# SensorStick_IMUedits.net
KiCad netlist of a schematic drawn in EAGLE
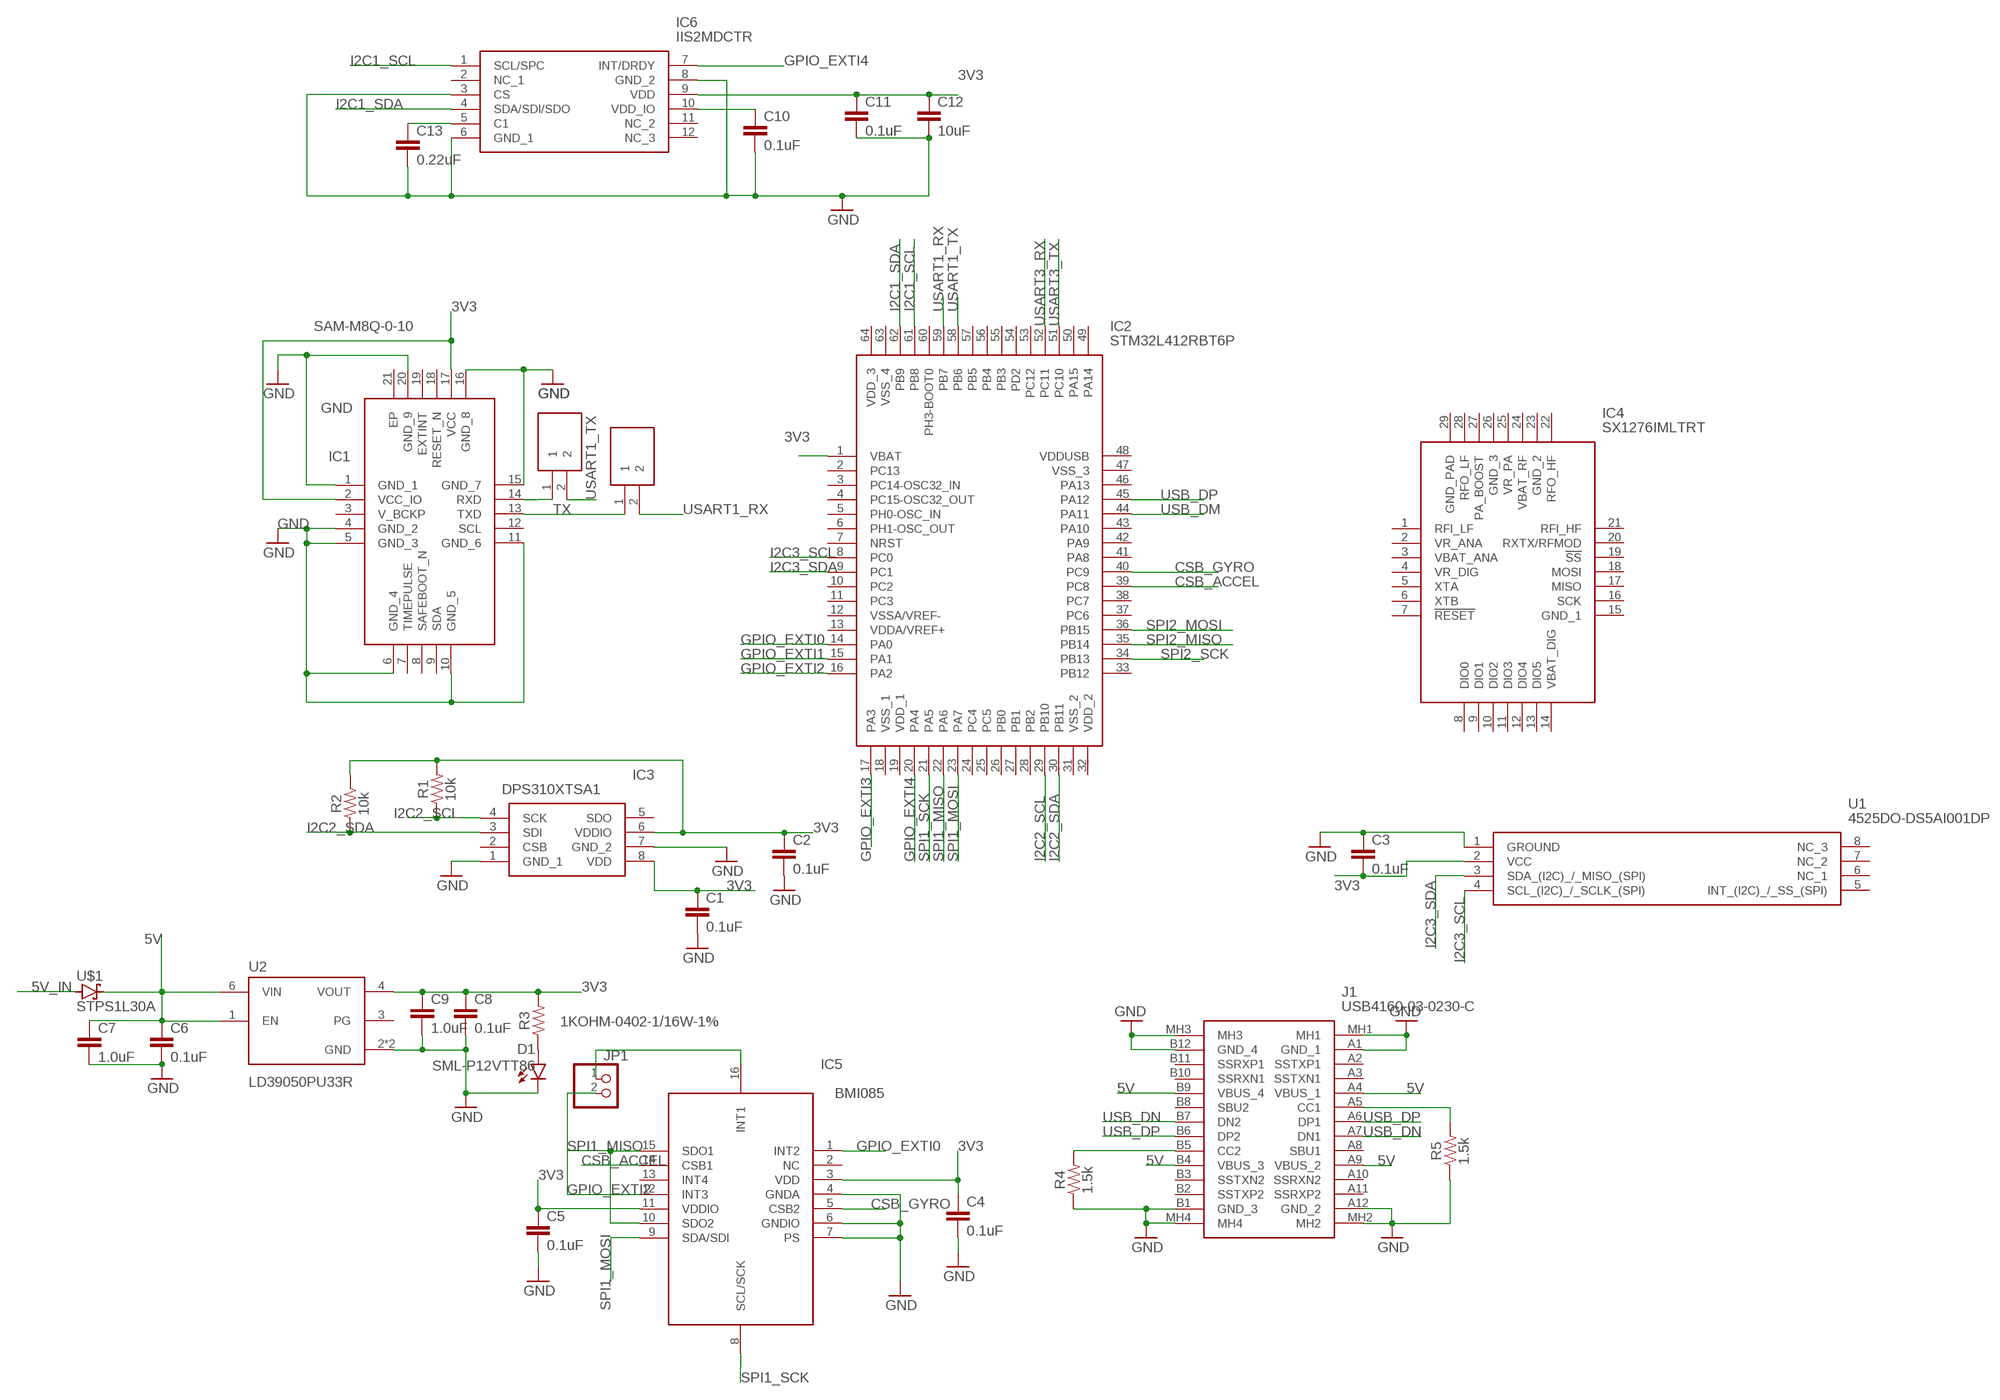
[diagram p0: schematic, sheet 1]

(export (version "E")
  (design (tool "Eeschema 10.0.6"))
  (components
    (comp (ref "C1")
      (value "0.1uF")
      (footprint "eagle-import:0402")
      (libsource (lib "eagle-import") (part "0.1UF-0402-6.3V-10%-X7R"))
    )
    (comp (ref "C2")
      (value "0.1uF")
      (footprint "eagle-import:0402")
      (libsource (lib "eagle-import") (part "0.1UF-0402-6.3V-10%-X7R"))
    )
    (comp (ref "C3")
      (value "0.1uF")
      (footprint "eagle-import:0402")
      (libsource (lib "eagle-import") (part "0.1UF-0402-6.3V-10%-X7R"))
    )
    (comp (ref "C4")
      (value "0.1uF")
      (footprint "eagle-import:0402")
      (libsource (lib "eagle-import") (part "0.1UF-0402-6.3V-10%-X7R"))
    )
    (comp (ref "C5")
      (value "0.1uF")
      (footprint "eagle-import:0402")
      (libsource (lib "eagle-import") (part "0.1UF-0402-6.3V-10%-X7R"))
    )
    (comp (ref "C6")
      (value "0.1uF")
      (footprint "eagle-import:0402")
      (libsource (lib "eagle-import") (part "0.1UF-0402-6.3V-10%-X7R"))
    )
    (comp (ref "C7")
      (value "1.0uF")
      (footprint "eagle-import:0402")
      (libsource (lib "eagle-import") (part "1.0UF-0402-16V-10%"))
    )
    (comp (ref "C8")
      (value "0.1uF")
      (footprint "eagle-import:0402")
      (libsource (lib "eagle-import") (part "0.1UF-0402-6.3V-10%-X7R"))
    )
    (comp (ref "C9")
      (value "1.0uF")
      (footprint "eagle-import:0402")
      (libsource (lib "eagle-import") (part "1.0UF-0402-16V-10%"))
    )
    (comp (ref "C10")
      (value "0.1uF")
      (footprint "eagle-import:0402")
      (libsource (lib "eagle-import") (part "0.1UF-0402-6.3V-10%-X7R"))
    )
    (comp (ref "C11")
      (value "0.1uF")
      (footprint "eagle-import:0402")
      (libsource (lib "eagle-import") (part "0.1UF-0402-6.3V-10%-X7R"))
    )
    (comp (ref "C12")
      (value "10uF")
      (footprint "eagle-import:0603")
      (libsource (lib "eagle-import") (part "10UF-0603-6.3V-20%"))
    )
    (comp (ref "C13")
      (value "0.22uF")
      (footprint "eagle-import:0603")
      (libsource (lib "eagle-import") (part "0.22UF-0603-25V-10%"))
    )
    (comp (ref "D1")
      (value "SML-P12VTT86")
      (footprint "eagle-import:LED_SML-P11UTT86R")
      (fields (field (name "MF") "Rohm"))
      (libsource (lib "eagle-import") (part "SML-P12VTT86"))
    )
    (comp (ref "FB1")
      (value "BLM15HD102SN1")
      (footprint "eagle-import:NFZ15SG152SN10B")
      (libsource (lib "eagle-import") (part "BLM15HD102SN1"))
    )
    (comp (ref "FB2")
      (value "BLM15HD102SN1")
      (footprint "eagle-import:NFZ15SG152SN10B")
      (libsource (lib "eagle-import") (part "BLM15HD102SN1"))
    )
    (comp (ref "IC1")
      (value "SAM-M8Q-0-10")
      (footprint "eagle-import:SAMM8Q010")
      (libsource (lib "eagle-import") (part "SAM-M8Q-0-10"))
    )
    (comp (ref "IC2")
      (value "STM32L412RBT6P")
      (footprint "eagle-import:QFP50P1200X1200X160-64N")
      (fields (field (name "MOUSER_PART_NUMBER") "511-STM32L412RBT6P"))
      (libsource (lib "eagle-import") (part "STM32L412RBT6P"))
    )
    (comp (ref "IC3")
      (value "DPS310XTSA1")
      (footprint "eagle-import:DPS310XTSA1")
      (fields (field (name "MOUSER_PART_NUMBER") "726-DPS310XTSA1"))
      (libsource (lib "eagle-import") (part "DPS310XTSA1"))
    )
    (comp (ref "IC4")
      (value "SX1276IMLTRT")
      (footprint "eagle-import:QFN65P600X600X100-29N")
      (fields (field (name "MOUSER_PART_NUMBER") "947-SX1276IMLTRT"))
      (libsource (lib "eagle-import") (part "SX1276IMLTRT"))
    )
    (comp (ref "IC5")
      (value "BMI085")
      (footprint "eagle-import:BMI085")
      (fields (field (name "MOUSER_PART_NUMBER") "262-BMI085"))
      (libsource (lib "eagle-import") (part "BMI085"))
    )
    (comp (ref "IC6")
      (value "IIS2MDCTR")
      (footprint "eagle-import:IIS2MDCTR")
      (fields (field (name "MOUSER_PART_NUMBER") "511-IIS2MDCTR"))
      (libsource (lib "eagle-import") (part "IIS2MDCTR"))
    )
    (comp (ref "J1")
      (value "USB4160-03-0230-C")
      (footprint "eagle-import:USB4160030230C")
      (fields (field (name "MOUSER_PART_NUMBER") "640-USB4160-3-0230-C"))
      (libsource (lib "eagle-import") (part "USB4160-03-0230-C"))
    )
    (comp (ref "JP1")
      (value "PINHD-1X2")
      (footprint "eagle-import:1X02")
      (libsource (lib "eagle-import") (part "PINHD-1X2"))
    )
    (comp (ref "R1")
      (value "10k")
      (footprint "eagle-import:0402")
      (libsource (lib "eagle-import") (part "10KOHM-0402-1/16W-1%"))
    )
    (comp (ref "R2")
      (value "10k")
      (footprint "eagle-import:0402")
      (libsource (lib "eagle-import") (part "10KOHM-0402-1/16W-1%"))
    )
    (comp (ref "R3")
      (value "1KOHM-0402-1/16W-1%")
      (footprint "eagle-import:0402")
      (libsource (lib "eagle-import") (part "1KOHM-0402-1/16W-1%"))
    )
    (comp (ref "R4")
      (value "1.5k")
      (footprint "eagle-import:0603")
      (libsource (lib "eagle-import") (part "1.5KOHM-0603-1/10W-1%"))
    )
    (comp (ref "R5")
      (value "1.5k")
      (footprint "eagle-import:0603")
      (libsource (lib "eagle-import") (part "1.5KOHM-0603-1/10W-1%"))
    )
    (comp (ref "U$1")
      (value "STPS1L30A")
      (footprint "eagle-import:DIOM5226X223N")
      (libsource (lib "eagle-import") (part "STPS1L30A"))
    )
    (comp (ref "U1")
      (value "4525DO-DS5AI001DP")
      (footprint "eagle-import:4525DO-DS...P")
      (fields (field (name "MOUSER_PART_NUMBER") "824-4525DODS5AI001DP"))
      (libsource (lib "eagle-import") (part "4525DO-DS5AI001DP"))
    )
    (comp (ref "U2")
      (value "LD39050PU33R")
      (footprint "eagle-import:SON95P300X300X100-7N")
      (fields (field (name "MF") "STMicroelectronics"))
      (libsource (lib "eagle-import") (part "LD39050PU33R"))
    )
  )
  (nets
    (net (code "1") (name "/3V3") (class "Default")
      (node (ref "C1") (pin "1") (pinfunction "1_1") (pintype "passive"))
      (node (ref "C11") (pin "1") (pinfunction "1_1") (pintype "passive"))
      (node (ref "C12") (pin "1") (pinfunction "1_1") (pintype "passive"))
      (node (ref "C2") (pin "1") (pinfunction "1_1") (pintype "passive"))
      (node (ref "C3") (pin "2") (pinfunction "2_2") (pintype "passive"))
      (node (ref "C4") (pin "1") (pinfunction "1_1") (pintype "passive"))
      (node (ref "C5") (pin "1") (pinfunction "1_1") (pintype "passive"))
      (node (ref "C8") (pin "1") (pinfunction "1_1") (pintype "passive"))
      (node (ref "C9") (pin "1") (pinfunction "1_1") (pintype "passive"))
      (node (ref "IC1") (pin "17") (pinfunction "VCC_17") (pintype "bidirectional"))
      (node (ref "IC1") (pin "2") (pinfunction "VCC_IO_2") (pintype "bidirectional"))
      (node (ref "IC2") (pin "1") (pinfunction "VBAT_1") (pintype "bidirectional"))
      (node (ref "IC3") (pin "6") (pinfunction "VDDIO_6") (pintype "bidirectional"))
      (node (ref "IC3") (pin "8") (pinfunction "VDD_8") (pintype "bidirectional"))
      (node (ref "IC5") (pin "11") (pinfunction "VDDIO_11") (pintype "bidirectional"))
      (node (ref "IC5") (pin "3") (pinfunction "VDD_3") (pintype "bidirectional"))
      (node (ref "IC6") (pin "9") (pinfunction "VDD_9") (pintype "bidirectional"))
      (node (ref "R1") (pin "2") (pinfunction "2_2") (pintype "passive"))
      (node (ref "R2") (pin "2") (pinfunction "2_2") (pintype "passive"))
      (node (ref "R3") (pin "2") (pinfunction "2_2") (pintype "passive"))
      (node (ref "U1") (pin "2") (pinfunction "VCC_2") (pintype "power_in"))
      (node (ref "U2") (pin "4") (pinfunction "VOUT_4") (pintype "output"))
    )
    (net (code "2") (name "/5V") (class "Default")
      (node (ref "C6") (pin "1") (pinfunction "1_1") (pintype "passive"))
      (node (ref "C7") (pin "1") (pinfunction "1_1") (pintype "passive"))
      (node (ref "J1") (pin "A4") (pinfunction "VBUS_1_A4") (pintype "bidirectional"))
      (node (ref "J1") (pin "A9") (pinfunction "VBUS_2_A9") (pintype "bidirectional"))
      (node (ref "J1") (pin "B4") (pinfunction "VBUS_3_B4") (pintype "bidirectional"))
      (node (ref "J1") (pin "B9") (pinfunction "VBUS_4_B9") (pintype "bidirectional"))
      (node (ref "U$1") (pin "1") (pinfunction "C_1") (pintype "passive"))
      (node (ref "U2") (pin "1") (pinfunction "EN_1") (pintype "input"))
      (node (ref "U2") (pin "6") (pinfunction "VIN_6") (pintype "power_in"))
    )
    (net (code "3") (name "/5V_IN") (class "Default")
      (node (ref "U$1") (pin "2") (pinfunction "A_2") (pintype "passive"))
    )
    (net (code "4") (name "/CSB_ACCEL") (class "Default")
      (node (ref "IC2") (pin "39") (pinfunction "PC8_39") (pintype "bidirectional"))
      (node (ref "IC5") (pin "14") (pinfunction "CSB1_14") (pintype "bidirectional"))
    )
    (net (code "5") (name "/CSB_GYRO") (class "Default")
      (node (ref "IC2") (pin "40") (pinfunction "PC9_40") (pintype "bidirectional"))
      (node (ref "IC5") (pin "5") (pinfunction "CSB2_5") (pintype "bidirectional"))
    )
    (net (code "6") (name "/GPIO_EXTI0") (class "Default")
      (node (ref "IC2") (pin "14") (pinfunction "PA0_14") (pintype "bidirectional"))
      (node (ref "IC5") (pin "1") (pinfunction "INT2_1") (pintype "bidirectional"))
    )
    (net (code "7") (name "/GPIO_EXTI1") (class "Default")
      (node (ref "IC2") (pin "15") (pinfunction "PA1_15") (pintype "bidirectional"))
    )
    (net (code "8") (name "/GPIO_EXTI2") (class "Default")
      (node (ref "IC2") (pin "16") (pinfunction "PA2_16") (pintype "bidirectional"))
      (node (ref "IC5") (pin "12") (pinfunction "INT3_12") (pintype "bidirectional"))
      (node (ref "JP1") (pin "2") (pinfunction "2_2") (pintype "passive"))
    )
    (net (code "9") (name "/GPIO_EXTI3") (class "Default")
      (node (ref "IC2") (pin "17") (pinfunction "PA3_17") (pintype "bidirectional"))
    )
    (net (code "10") (name "/GPIO_EXTI4") (class "Default")
      (node (ref "IC2") (pin "20") (pinfunction "PA4_20") (pintype "bidirectional"))
      (node (ref "IC6") (pin "7") (pinfunction "INT/DRDY_7") (pintype "bidirectional"))
    )
    (net (code "11") (name "/I2C1_SCL") (class "Default")
      (node (ref "IC2") (pin "61") (pinfunction "PB8_61") (pintype "bidirectional"))
      (node (ref "IC6") (pin "1") (pinfunction "SCL/SPC_1") (pintype "bidirectional"))
    )
    (net (code "12") (name "/I2C1_SDA") (class "Default")
      (node (ref "IC2") (pin "62") (pinfunction "PB9_62") (pintype "bidirectional"))
      (node (ref "IC6") (pin "4") (pinfunction "SDA/SDI/SDO_4") (pintype "bidirectional"))
    )
    (net (code "13") (name "/I2C2_SCL") (class "Default")
      (node (ref "IC2") (pin "29") (pinfunction "PB10_29") (pintype "bidirectional"))
      (node (ref "IC3") (pin "4") (pinfunction "SCK_4") (pintype "bidirectional"))
      (node (ref "R1") (pin "1") (pinfunction "1_1") (pintype "passive"))
    )
    (net (code "14") (name "/I2C2_SDA") (class "Default")
      (node (ref "IC2") (pin "30") (pinfunction "PB11_30") (pintype "bidirectional"))
      (node (ref "IC3") (pin "3") (pinfunction "SDI_3") (pintype "bidirectional"))
      (node (ref "R2") (pin "1") (pinfunction "1_1") (pintype "passive"))
    )
    (net (code "15") (name "/I2C3_SCL") (class "Default")
      (node (ref "IC2") (pin "8") (pinfunction "PC0_8") (pintype "bidirectional"))
      (node (ref "U1") (pin "4") (pinfunction "SCL_(I2C)_/_SCLK_(SPI)_4") (pintype "bidirectional"))
    )
    (net (code "16") (name "/I2C3_SDA") (class "Default")
      (node (ref "IC2") (pin "9") (pinfunction "PC1_9") (pintype "bidirectional"))
      (node (ref "U1") (pin "3") (pinfunction "SDA_(I2C)_/_MISO_(SPI)_3") (pintype "bidirectional"))
    )
    (net (code "17") (name "/SPI1_MISO") (class "Default")
      (node (ref "IC2") (pin "22") (pinfunction "PA6_22") (pintype "bidirectional"))
      (node (ref "IC5") (pin "10") (pinfunction "SDO2_10") (pintype "bidirectional"))
      (node (ref "IC5") (pin "15") (pinfunction "SDO1_15") (pintype "bidirectional"))
    )
    (net (code "18") (name "/SPI1_MOSI") (class "Default")
      (node (ref "IC2") (pin "23") (pinfunction "PA7_23") (pintype "bidirectional"))
      (node (ref "IC5") (pin "9") (pinfunction "SDA/SDI_9") (pintype "bidirectional"))
    )
    (net (code "19") (name "/SPI1_SCK") (class "Default")
      (node (ref "IC2") (pin "21") (pinfunction "PA5_21") (pintype "bidirectional"))
      (node (ref "IC5") (pin "8") (pinfunction "SCL/SCK_8") (pintype "bidirectional"))
    )
    (net (code "20") (name "/SPI2_MISO") (class "Default")
      (node (ref "IC2") (pin "35") (pinfunction "PB14_35") (pintype "bidirectional"))
    )
    (net (code "21") (name "/SPI2_MOSI") (class "Default")
      (node (ref "IC2") (pin "36") (pinfunction "PB15_36") (pintype "bidirectional"))
    )
    (net (code "22") (name "/SPI2_SCK") (class "Default")
      (node (ref "IC2") (pin "34") (pinfunction "PB13_34") (pintype "bidirectional"))
    )
    (net (code "23") (name "/TX") (class "Default")
      (node (ref "FB1") (pin "1") (pinfunction "1_1") (pintype "bidirectional"))
      (node (ref "IC1") (pin "13") (pinfunction "TXD_13") (pintype "bidirectional"))
    )
    (net (code "24") (name "/USART1_RX") (class "Default")
      (node (ref "FB1") (pin "2") (pinfunction "2_2") (pintype "bidirectional"))
      (node (ref "IC2") (pin "59") (pinfunction "PB7_59") (pintype "bidirectional"))
    )
    (net (code "25") (name "/USART1_TX") (class "Default")
      (node (ref "FB2") (pin "2") (pinfunction "2_2") (pintype "bidirectional"))
      (node (ref "IC2") (pin "58") (pinfunction "PB6_58") (pintype "bidirectional"))
    )
    (net (code "26") (name "/USART3_RX") (class "Default")
      (node (ref "IC2") (pin "52") (pinfunction "PC11_52") (pintype "bidirectional"))
    )
    (net (code "27") (name "/USART3_TX") (class "Default")
      (node (ref "IC2") (pin "51") (pinfunction "PC10_51") (pintype "bidirectional"))
    )
    (net (code "28") (name "/USB_DM") (class "Default")
      (node (ref "IC2") (pin "44") (pinfunction "PA11_44") (pintype "bidirectional"))
    )
    (net (code "29") (name "/USB_DN") (class "Default")
      (node (ref "J1") (pin "A7") (pinfunction "DN1_A7") (pintype "bidirectional"))
      (node (ref "J1") (pin "B7") (pinfunction "DN2_B7") (pintype "bidirectional"))
    )
    (net (code "30") (name "/USB_DP") (class "Default")
      (node (ref "IC2") (pin "45") (pinfunction "PA12_45") (pintype "bidirectional"))
      (node (ref "J1") (pin "A6") (pinfunction "DP1_A6") (pintype "bidirectional"))
      (node (ref "J1") (pin "B6") (pinfunction "DP2_B6") (pintype "bidirectional"))
    )
    (net (code "31") (name "GND") (class "Default")
      (node (ref "C1") (pin "2") (pinfunction "2_2") (pintype "passive"))
      (node (ref "C10") (pin "2") (pinfunction "2_2") (pintype "passive"))
      (node (ref "C11") (pin "2") (pinfunction "2_2") (pintype "passive"))
      (node (ref "C12") (pin "2") (pinfunction "2_2") (pintype "passive"))
      (node (ref "C13") (pin "2") (pinfunction "2_2") (pintype "passive"))
      (node (ref "C2") (pin "2") (pinfunction "2_2") (pintype "passive"))
      (node (ref "C3") (pin "1") (pinfunction "1_1") (pintype "passive"))
      (node (ref "C4") (pin "2") (pinfunction "2_2") (pintype "passive"))
      (node (ref "C5") (pin "2") (pinfunction "2_2") (pintype "passive"))
      (node (ref "C6") (pin "2") (pinfunction "2_2") (pintype "passive"))
      (node (ref "C7") (pin "2") (pinfunction "2_2") (pintype "passive"))
      (node (ref "C8") (pin "2") (pinfunction "2_2") (pintype "passive"))
      (node (ref "C9") (pin "2") (pinfunction "2_2") (pintype "passive"))
      (node (ref "D1") (pin "C") (pinfunction "C_C") (pintype "passive"))
      (node (ref "IC1") (pin "1") (pinfunction "GND_1_1") (pintype "bidirectional"))
      (node (ref "IC1") (pin "10") (pinfunction "GND_5_10") (pintype "bidirectional"))
      (node (ref "IC1") (pin "11") (pinfunction "GND_6_11") (pintype "bidirectional"))
      (node (ref "IC1") (pin "15") (pinfunction "GND_7_15") (pintype "bidirectional"))
      (node (ref "IC1") (pin "16") (pinfunction "GND_8_16") (pintype "bidirectional"))
      (node (ref "IC1") (pin "20") (pinfunction "GND_9_20") (pintype "bidirectional"))
      (node (ref "IC1") (pin "4") (pinfunction "GND_2_4") (pintype "bidirectional"))
      (node (ref "IC1") (pin "5") (pinfunction "GND_3_5") (pintype "bidirectional"))
      (node (ref "IC1") (pin "6") (pinfunction "GND_4_6") (pintype "bidirectional"))
      (node (ref "IC3") (pin "1") (pinfunction "GND_1_1") (pintype "bidirectional"))
      (node (ref "IC3") (pin "7") (pinfunction "GND_2_7") (pintype "bidirectional"))
      (node (ref "IC5") (pin "4") (pinfunction "GNDA_4") (pintype "bidirectional"))
      (node (ref "IC5") (pin "6") (pinfunction "GNDIO_6") (pintype "bidirectional"))
      (node (ref "IC5") (pin "7") (pinfunction "PS_7") (pintype "bidirectional"))
      (node (ref "IC6") (pin "3") (pinfunction "CS_3") (pintype "bidirectional"))
      (node (ref "IC6") (pin "6") (pinfunction "GND_1_6") (pintype "bidirectional"))
      (node (ref "IC6") (pin "8") (pinfunction "GND_2_8") (pintype "bidirectional"))
      (node (ref "J1") (pin "A1") (pinfunction "GND_1_A1") (pintype "bidirectional"))
      (node (ref "J1") (pin "A12") (pinfunction "GND_2_A12") (pintype "bidirectional"))
      (node (ref "J1") (pin "B1") (pinfunction "GND_3_B1") (pintype "bidirectional"))
      (node (ref "J1") (pin "B12") (pinfunction "GND_4_B12") (pintype "bidirectional"))
      (node (ref "J1") (pin "MH1") (pinfunction "MH1_MH1") (pintype "bidirectional"))
      (node (ref "J1") (pin "MH2") (pinfunction "MH2_MH2") (pintype "bidirectional"))
      (node (ref "J1") (pin "MH3") (pinfunction "MH3_MH3") (pintype "bidirectional"))
      (node (ref "J1") (pin "MH4") (pinfunction "MH4_MH4") (pintype "bidirectional"))
      (node (ref "R4") (pin "1") (pinfunction "1_1") (pintype "passive"))
      (node (ref "R5") (pin "1") (pinfunction "1_1") (pintype "passive"))
      (node (ref "U1") (pin "1") (pinfunction "GROUND_1") (pintype "power_in"))
      (node (ref "U2") (pin "2") (pinfunction "GND_2") (pintype "power_in"))
      (node (ref "U2") (pin "7") (pinfunction "GND_7") (pintype "power_in"))
    )
    (net (code "32") (name "Net-(D1-PadA)") (class "Default")
      (node (ref "D1") (pin "A") (pinfunction "A_A") (pintype "passive"))
      (node (ref "R3") (pin "1") (pinfunction "1_1") (pintype "passive"))
    )
    (net (code "33") (name "Net-(IC1-RXD)") (class "Default")
      (node (ref "FB2") (pin "1") (pinfunction "1_1") (pintype "bidirectional"))
      (node (ref "IC1") (pin "14") (pinfunction "RXD_14") (pintype "bidirectional"))
    )
    (net (code "34") (name "Net-(IC5-INT1)") (class "Default")
      (node (ref "IC5") (pin "16") (pinfunction "INT1_16") (pintype "bidirectional"))
      (node (ref "JP1") (pin "1") (pinfunction "1_1") (pintype "passive"))
    )
    (net (code "35") (name "Net-(IC6-C1)") (class "Default")
      (node (ref "C13") (pin "1") (pinfunction "1_1") (pintype "passive"))
      (node (ref "IC6") (pin "5") (pinfunction "C1_5") (pintype "bidirectional"))
    )
    (net (code "36") (name "Net-(IC6-VDD_IO)") (class "Default")
      (node (ref "C10") (pin "1") (pinfunction "1_1") (pintype "passive"))
      (node (ref "IC6") (pin "10") (pinfunction "VDD_IO_10") (pintype "bidirectional"))
    )
    (net (code "37") (name "Net-(J1-CC1)") (class "Default")
      (node (ref "J1") (pin "A5") (pinfunction "CC1_A5") (pintype "bidirectional"))
      (node (ref "R5") (pin "2") (pinfunction "2_2") (pintype "passive"))
    )
    (net (code "38") (name "Net-(J1-CC2)") (class "Default")
      (node (ref "J1") (pin "B5") (pinfunction "CC2_B5") (pintype "bidirectional"))
      (node (ref "R4") (pin "2") (pinfunction "2_2") (pintype "passive"))
    )
    (net (code "39") (name "unconnected-(IC1-EP-Pad21)") (class "Default")
      (node (ref "IC1") (pin "21") (pinfunction "EP_21") (pintype "bidirectional"))
    )
    (net (code "40") (name "unconnected-(IC1-EXTINT-Pad19)") (class "Default")
      (node (ref "IC1") (pin "19") (pinfunction "EXTINT_19") (pintype "bidirectional"))
    )
    (net (code "41") (name "unconnected-(IC1-RESET_N-Pad18)") (class "Default")
      (node (ref "IC1") (pin "18") (pinfunction "RESET_N_18") (pintype "bidirectional"))
    )
    (net (code "42") (name "unconnected-(IC1-SAFEBOOT_N-Pad8)") (class "Default")
      (node (ref "IC1") (pin "8") (pinfunction "SAFEBOOT_N_8") (pintype "bidirectional"))
    )
    (net (code "43") (name "unconnected-(IC1-SCL-Pad12)") (class "Default")
      (node (ref "IC1") (pin "12") (pinfunction "SCL_12") (pintype "bidirectional"))
    )
    (net (code "44") (name "unconnected-(IC1-SDA-Pad9)") (class "Default")
      (node (ref "IC1") (pin "9") (pinfunction "SDA_9") (pintype "bidirectional"))
    )
    (net (code "45") (name "unconnected-(IC1-TIMEPULSE-Pad7)") (class "Default")
      (node (ref "IC1") (pin "7") (pinfunction "TIMEPULSE_7") (pintype "bidirectional"))
    )
    (net (code "46") (name "unconnected-(IC1-V_BCKP-Pad3)") (class "Default")
      (node (ref "IC1") (pin "3") (pinfunction "V_BCKP_3") (pintype "bidirectional"))
    )
    (net (code "47") (name "unconnected-(IC2-NRST-Pad7)") (class "Default")
      (node (ref "IC2") (pin "7") (pinfunction "NRST_7") (pintype "bidirectional"))
    )
    (net (code "48") (name "unconnected-(IC2-PA8-Pad41)") (class "Default")
      (node (ref "IC2") (pin "41") (pinfunction "PA8_41") (pintype "bidirectional"))
    )
    (net (code "49") (name "unconnected-(IC2-PA9-Pad42)") (class "Default")
      (node (ref "IC2") (pin "42") (pinfunction "PA9_42") (pintype "bidirectional"))
    )
    (net (code "50") (name "unconnected-(IC2-PA10-Pad43)") (class "Default")
      (node (ref "IC2") (pin "43") (pinfunction "PA10_43") (pintype "bidirectional"))
    )
    (net (code "51") (name "unconnected-(IC2-PA13-Pad46)") (class "Default")
      (node (ref "IC2") (pin "46") (pinfunction "PA13_46") (pintype "bidirectional"))
    )
    (net (code "52") (name "unconnected-(IC2-PA14-Pad49)") (class "Default")
      (node (ref "IC2") (pin "49") (pinfunction "PA14_49") (pintype "bidirectional"))
    )
    (net (code "53") (name "unconnected-(IC2-PA15-Pad50)") (class "Default")
      (node (ref "IC2") (pin "50") (pinfunction "PA15_50") (pintype "bidirectional"))
    )
    (net (code "54") (name "unconnected-(IC2-PB0-Pad26)") (class "Default")
      (node (ref "IC2") (pin "26") (pinfunction "PB0_26") (pintype "bidirectional"))
    )
    (net (code "55") (name "unconnected-(IC2-PB1-Pad27)") (class "Default")
      (node (ref "IC2") (pin "27") (pinfunction "PB1_27") (pintype "bidirectional"))
    )
    (net (code "56") (name "unconnected-(IC2-PB2-Pad28)") (class "Default")
      (node (ref "IC2") (pin "28") (pinfunction "PB2_28") (pintype "bidirectional"))
    )
    (net (code "57") (name "unconnected-(IC2-PB3-Pad55)") (class "Default")
      (node (ref "IC2") (pin "55") (pinfunction "PB3_55") (pintype "bidirectional"))
    )
    (net (code "58") (name "unconnected-(IC2-PB4-Pad56)") (class "Default")
      (node (ref "IC2") (pin "56") (pinfunction "PB4_56") (pintype "bidirectional"))
    )
    (net (code "59") (name "unconnected-(IC2-PB5-Pad57)") (class "Default")
      (node (ref "IC2") (pin "57") (pinfunction "PB5_57") (pintype "bidirectional"))
    )
    (net (code "60") (name "unconnected-(IC2-PB12-Pad33)") (class "Default")
      (node (ref "IC2") (pin "33") (pinfunction "PB12_33") (pintype "bidirectional"))
    )
    (net (code "61") (name "unconnected-(IC2-PC2-Pad10)") (class "Default")
      (node (ref "IC2") (pin "10") (pinfunction "PC2_10") (pintype "bidirectional"))
    )
    (net (code "62") (name "unconnected-(IC2-PC3-Pad11)") (class "Default")
      (node (ref "IC2") (pin "11") (pinfunction "PC3_11") (pintype "bidirectional"))
    )
    (net (code "63") (name "unconnected-(IC2-PC4-Pad24)") (class "Default")
      (node (ref "IC2") (pin "24") (pinfunction "PC4_24") (pintype "bidirectional"))
    )
    (net (code "64") (name "unconnected-(IC2-PC5-Pad25)") (class "Default")
      (node (ref "IC2") (pin "25") (pinfunction "PC5_25") (pintype "bidirectional"))
    )
    (net (code "65") (name "unconnected-(IC2-PC6-Pad37)") (class "Default")
      (node (ref "IC2") (pin "37") (pinfunction "PC6_37") (pintype "bidirectional"))
    )
    (net (code "66") (name "unconnected-(IC2-PC7-Pad38)") (class "Default")
      (node (ref "IC2") (pin "38") (pinfunction "PC7_38") (pintype "bidirectional"))
    )
    (net (code "67") (name "unconnected-(IC2-PC12-Pad53)") (class "Default")
      (node (ref "IC2") (pin "53") (pinfunction "PC12_53") (pintype "bidirectional"))
    )
    (net (code "68") (name "unconnected-(IC2-PC13-Pad2)") (class "Default")
      (node (ref "IC2") (pin "2") (pinfunction "PC13_2") (pintype "bidirectional"))
    )
    (net (code "69") (name "unconnected-(IC2-PC14-OSC32_IN-Pad3)") (class "Default")
      (node (ref "IC2") (pin "3") (pinfunction "PC14-OSC32_IN_3") (pintype "bidirectional"))
    )
    (net (code "70") (name "unconnected-(IC2-PC15-OSC32_OUT-Pad4)") (class "Default")
      (node (ref "IC2") (pin "4") (pinfunction "PC15-OSC32_OUT_4") (pintype "bidirectional"))
    )
    (net (code "71") (name "unconnected-(IC2-PD2-Pad54)") (class "Default")
      (node (ref "IC2") (pin "54") (pinfunction "PD2_54") (pintype "bidirectional"))
    )
    (net (code "72") (name "unconnected-(IC2-PH0-OSC_IN-Pad5)") (class "Default")
      (node (ref "IC2") (pin "5") (pinfunction "PH0-OSC_IN_5") (pintype "bidirectional"))
    )
    (net (code "73") (name "unconnected-(IC2-PH1-OSC_OUT-Pad6)") (class "Default")
      (node (ref "IC2") (pin "6") (pinfunction "PH1-OSC_OUT_6") (pintype "bidirectional"))
    )
    (net (code "74") (name "unconnected-(IC2-PH3-BOOT0-Pad60)") (class "Default")
      (node (ref "IC2") (pin "60") (pinfunction "PH3-BOOT0_60") (pintype "bidirectional"))
    )
    (net (code "75") (name "unconnected-(IC2-VDDA{slash}VREF+-Pad13)") (class "Default")
      (node (ref "IC2") (pin "13") (pinfunction "VDDA/VREF+_13") (pintype "bidirectional"))
    )
    (net (code "76") (name "unconnected-(IC2-VDDUSB-Pad48)") (class "Default")
      (node (ref "IC2") (pin "48") (pinfunction "VDDUSB_48") (pintype "bidirectional"))
    )
    (net (code "77") (name "unconnected-(IC2-VDD_1-Pad19)") (class "Default")
      (node (ref "IC2") (pin "19") (pinfunction "VDD_1_19") (pintype "bidirectional"))
    )
    (net (code "78") (name "unconnected-(IC2-VDD_2-Pad32)") (class "Default")
      (node (ref "IC2") (pin "32") (pinfunction "VDD_2_32") (pintype "bidirectional"))
    )
    (net (code "79") (name "unconnected-(IC2-VDD_3-Pad64)") (class "Default")
      (node (ref "IC2") (pin "64") (pinfunction "VDD_3_64") (pintype "bidirectional"))
    )
    (net (code "80") (name "unconnected-(IC2-VSSA{slash}VREF--Pad12)") (class "Default")
      (node (ref "IC2") (pin "12") (pinfunction "VSSA/VREF-_12") (pintype "bidirectional"))
    )
    (net (code "81") (name "unconnected-(IC2-VSS_1-Pad18)") (class "Default")
      (node (ref "IC2") (pin "18") (pinfunction "VSS_1_18") (pintype "bidirectional"))
    )
    (net (code "82") (name "unconnected-(IC2-VSS_2-Pad31)") (class "Default")
      (node (ref "IC2") (pin "31") (pinfunction "VSS_2_31") (pintype "bidirectional"))
    )
    (net (code "83") (name "unconnected-(IC2-VSS_3-Pad47)") (class "Default")
      (node (ref "IC2") (pin "47") (pinfunction "VSS_3_47") (pintype "bidirectional"))
    )
    (net (code "84") (name "unconnected-(IC2-VSS_4-Pad63)") (class "Default")
      (node (ref "IC2") (pin "63") (pinfunction "VSS_4_63") (pintype "bidirectional"))
    )
    (net (code "85") (name "unconnected-(IC3-CSB-Pad2)") (class "Default")
      (node (ref "IC3") (pin "2") (pinfunction "CSB_2") (pintype "bidirectional"))
    )
    (net (code "86") (name "unconnected-(IC3-SDO-Pad5)") (class "Default")
      (node (ref "IC3") (pin "5") (pinfunction "SDO_5") (pintype "bidirectional"))
    )
    (net (code "87") (name "unconnected-(IC4-DIO0-Pad8)") (class "Default")
      (node (ref "IC4") (pin "8") (pinfunction "DIO0_8") (pintype "bidirectional"))
    )
    (net (code "88") (name "unconnected-(IC4-DIO1-Pad9)") (class "Default")
      (node (ref "IC4") (pin "9") (pinfunction "DIO1_9") (pintype "bidirectional"))
    )
    (net (code "89") (name "unconnected-(IC4-DIO2-Pad10)") (class "Default")
      (node (ref "IC4") (pin "10") (pinfunction "DIO2_10") (pintype "bidirectional"))
    )
    (net (code "90") (name "unconnected-(IC4-DIO3-Pad11)") (class "Default")
      (node (ref "IC4") (pin "11") (pinfunction "DIO3_11") (pintype "bidirectional"))
    )
    (net (code "91") (name "unconnected-(IC4-DIO4-Pad12)") (class "Default")
      (node (ref "IC4") (pin "12") (pinfunction "DIO4_12") (pintype "bidirectional"))
    )
    (net (code "92") (name "unconnected-(IC4-DIO5-Pad13)") (class "Default")
      (node (ref "IC4") (pin "13") (pinfunction "DIO5_13") (pintype "bidirectional"))
    )
    (net (code "93") (name "unconnected-(IC4-GND_1-Pad15)") (class "Default")
      (node (ref "IC4") (pin "15") (pinfunction "GND_1_15") (pintype "bidirectional"))
    )
    (net (code "94") (name "unconnected-(IC4-GND_2-Pad23)") (class "Default")
      (node (ref "IC4") (pin "23") (pinfunction "GND_2_23") (pintype "bidirectional"))
    )
    (net (code "95") (name "unconnected-(IC4-GND_3-Pad26)") (class "Default")
      (node (ref "IC4") (pin "26") (pinfunction "GND_3_26") (pintype "bidirectional"))
    )
    (net (code "96") (name "unconnected-(IC4-GND_PAD-Pad29)") (class "Default")
      (node (ref "IC4") (pin "29") (pinfunction "GND_PAD_29") (pintype "bidirectional"))
    )
    (net (code "97") (name "unconnected-(IC4-MISO-Pad17)") (class "Default")
      (node (ref "IC4") (pin "17") (pinfunction "MISO_17") (pintype "bidirectional"))
    )
    (net (code "98") (name "unconnected-(IC4-MOSI-Pad18)") (class "Default")
      (node (ref "IC4") (pin "18") (pinfunction "MOSI_18") (pintype "bidirectional"))
    )
    (net (code "99") (name "unconnected-(IC4-PA_BOOST-Pad27)") (class "Default")
      (node (ref "IC4") (pin "27") (pinfunction "PA_BOOST_27") (pintype "bidirectional"))
    )
    (net (code "100") (name "unconnected-(IC4-RFI_HF-Pad21)") (class "Default")
      (node (ref "IC4") (pin "21") (pinfunction "RFI_HF_21") (pintype "bidirectional"))
    )
    (net (code "101") (name "unconnected-(IC4-RFI_LF-Pad1)") (class "Default")
      (node (ref "IC4") (pin "1") (pinfunction "RFI_LF_1") (pintype "bidirectional"))
    )
    (net (code "102") (name "unconnected-(IC4-RFO_HF-Pad22)") (class "Default")
      (node (ref "IC4") (pin "22") (pinfunction "RFO_HF_22") (pintype "bidirectional"))
    )
    (net (code "103") (name "unconnected-(IC4-RFO_LF-Pad28)") (class "Default")
      (node (ref "IC4") (pin "28") (pinfunction "RFO_LF_28") (pintype "bidirectional"))
    )
    (net (code "104") (name "unconnected-(IC4-RXTX{slash}RFMOD-Pad20)") (class "Default")
      (node (ref "IC4") (pin "20") (pinfunction "RXTX/RFMOD_20") (pintype "bidirectional"))
    )
    (net (code "105") (name "unconnected-(IC4-SCK-Pad16)") (class "Default")
      (node (ref "IC4") (pin "16") (pinfunction "SCK_16") (pintype "bidirectional"))
    )
    (net (code "106") (name "unconnected-(IC4-VBAT_ANA-Pad3)") (class "Default")
      (node (ref "IC4") (pin "3") (pinfunction "VBAT_ANA_3") (pintype "bidirectional"))
    )
    (net (code "107") (name "unconnected-(IC4-VBAT_DIG-Pad14)") (class "Default")
      (node (ref "IC4") (pin "14") (pinfunction "VBAT_DIG_14") (pintype "bidirectional"))
    )
    (net (code "108") (name "unconnected-(IC4-VBAT_RF-Pad24)") (class "Default")
      (node (ref "IC4") (pin "24") (pinfunction "VBAT_RF_24") (pintype "bidirectional"))
    )
    (net (code "109") (name "unconnected-(IC4-VR_ANA-Pad2)") (class "Default")
      (node (ref "IC4") (pin "2") (pinfunction "VR_ANA_2") (pintype "bidirectional"))
    )
    (net (code "110") (name "unconnected-(IC4-VR_DIG-Pad4)") (class "Default")
      (node (ref "IC4") (pin "4") (pinfunction "VR_DIG_4") (pintype "bidirectional"))
    )
    (net (code "111") (name "unconnected-(IC4-VR_PA-Pad25)") (class "Default")
      (node (ref "IC4") (pin "25") (pinfunction "VR_PA_25") (pintype "bidirectional"))
    )
    (net (code "112") (name "unconnected-(IC4-XTA-Pad5)") (class "Default")
      (node (ref "IC4") (pin "5") (pinfunction "XTA_5") (pintype "bidirectional"))
    )
    (net (code "113") (name "unconnected-(IC4-XTB-Pad6)") (class "Default")
      (node (ref "IC4") (pin "6") (pinfunction "XTB_6") (pintype "bidirectional"))
    )
    (net (code "114") (name "unconnected-(IC4-~{RESET}-Pad7)") (class "Default")
      (node (ref "IC4") (pin "7") (pinfunction "~{RESET}_7") (pintype "bidirectional"))
    )
    (net (code "115") (name "unconnected-(IC4-~{SS}-Pad19)") (class "Default")
      (node (ref "IC4") (pin "19") (pinfunction "~{SS}_19") (pintype "bidirectional"))
    )
    (net (code "116") (name "unconnected-(IC5-INT4-Pad13)") (class "Default")
      (node (ref "IC5") (pin "13") (pinfunction "INT4_13") (pintype "bidirectional"))
    )
    (net (code "117") (name "unconnected-(IC5-NC-Pad2)") (class "Default")
      (node (ref "IC5") (pin "2") (pinfunction "NC_2") (pintype "no_connect"))
    )
    (net (code "118") (name "unconnected-(IC6-NC_1-Pad2)") (class "Default")
      (node (ref "IC6") (pin "2") (pinfunction "NC_1_2") (pintype "bidirectional"))
    )
    (net (code "119") (name "unconnected-(IC6-NC_2-Pad11)") (class "Default")
      (node (ref "IC6") (pin "11") (pinfunction "NC_2_11") (pintype "bidirectional"))
    )
    (net (code "120") (name "unconnected-(IC6-NC_3-Pad12)") (class "Default")
      (node (ref "IC6") (pin "12") (pinfunction "NC_3_12") (pintype "bidirectional"))
    )
    (net (code "121") (name "unconnected-(J1-SBU1-PadA8)") (class "Default")
      (node (ref "J1") (pin "A8") (pinfunction "SBU1_A8") (pintype "bidirectional"))
    )
    (net (code "122") (name "unconnected-(J1-SBU2-PadB8)") (class "Default")
      (node (ref "J1") (pin "B8") (pinfunction "SBU2_B8") (pintype "bidirectional"))
    )
    (net (code "123") (name "unconnected-(J1-SSRXN1-PadB10)") (class "Default")
      (node (ref "J1") (pin "B10") (pinfunction "SSRXN1_B10") (pintype "bidirectional"))
    )
    (net (code "124") (name "unconnected-(J1-SSRXN2-PadA10)") (class "Default")
      (node (ref "J1") (pin "A10") (pinfunction "SSRXN2_A10") (pintype "bidirectional"))
    )
    (net (code "125") (name "unconnected-(J1-SSRXP1-PadB11)") (class "Default")
      (node (ref "J1") (pin "B11") (pinfunction "SSRXP1_B11") (pintype "bidirectional"))
    )
    (net (code "126") (name "unconnected-(J1-SSRXP2-PadA11)") (class "Default")
      (node (ref "J1") (pin "A11") (pinfunction "SSRXP2_A11") (pintype "bidirectional"))
    )
    (net (code "127") (name "unconnected-(J1-SSTXN1-PadA3)") (class "Default")
      (node (ref "J1") (pin "A3") (pinfunction "SSTXN1_A3") (pintype "bidirectional"))
    )
    (net (code "128") (name "unconnected-(J1-SSTXN2-PadB3)") (class "Default")
      (node (ref "J1") (pin "B3") (pinfunction "SSTXN2_B3") (pintype "bidirectional"))
    )
    (net (code "129") (name "unconnected-(J1-SSTXP1-PadA2)") (class "Default")
      (node (ref "J1") (pin "A2") (pinfunction "SSTXP1_A2") (pintype "bidirectional"))
    )
    (net (code "130") (name "unconnected-(J1-SSTXP2-PadB2)") (class "Default")
      (node (ref "J1") (pin "B2") (pinfunction "SSTXP2_B2") (pintype "bidirectional"))
    )
    (net (code "131") (name "unconnected-(U1-INT_(I2C)_{slash}_SS_(SPI)-Pad5)") (class "Default")
      (node (ref "U1") (pin "5") (pinfunction "INT_(I2C)_/_SS_(SPI)_5") (pintype "bidirectional"))
    )
    (net (code "132") (name "unconnected-(U1-NC_1-Pad6)") (class "Default")
      (node (ref "U1") (pin "6") (pinfunction "NC_1_6") (pintype "bidirectional"))
    )
    (net (code "133") (name "unconnected-(U1-NC_2-Pad7)") (class "Default")
      (node (ref "U1") (pin "7") (pinfunction "NC_2_7") (pintype "bidirectional"))
    )
    (net (code "134") (name "unconnected-(U1-NC_3-Pad8)") (class "Default")
      (node (ref "U1") (pin "8") (pinfunction "NC_3_8") (pintype "bidirectional"))
    )
    (net (code "135") (name "unconnected-(U2-PG-Pad3)") (class "Default")
      (node (ref "U2") (pin "3") (pinfunction "PG_3") (pintype "bidirectional"))
    )
  )
)
